# SH3_-_USB.net
KiCad netlist of a schematic drawn in Altium Designer
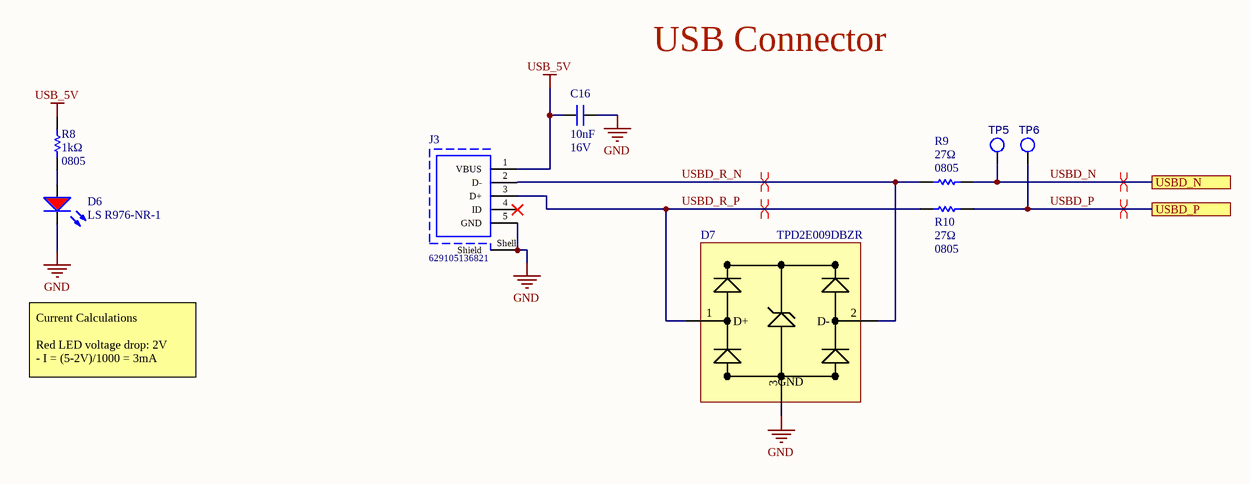
[diagram p0: SH3 - USB.SchDoc]

(export (version "E")
  (design (tool "Eeschema 10.0.6"))
  (components
    (comp (ref "C16")
      (value "CAP_10nF_16V_0805")
      (footprint "CAP2012")
      (description "CAP CER 10000PF 16V X7R 0805")
      (fields
        (field (name "VOLTAGE RATING") "16V")
        (field (name "TOLERANCE") "10%")
        (field (name "CAPACITANCE") "10nF")
      )
      (libsource (lib "UWRT_Schematic_Library_2020") (part "CAP_10nF_16V_0805"))
    )
    (comp (ref "D6")
      (value "LS R976-NR-1")
      (footprint "LED_0805_RED")
      (description "LED RED DIFFUSED 0805 SMD")
      (libsource (lib "UWRT_Schematic_Library_2020") (part "DIO_LED_R"))
    )
    (comp (ref "D7")
      (value "TVS_DIODE_USB_5.5V")
      (footprint "SOT23-3")
      (description "ESD Suppressor Diode Arrays 8KV 3-Pin SOT-23 T/R")
      (fields
        (field (name "MANUFACTURER") "Texas Instruments")
        (field (name "MANUFACTURER PART NUMBER") "TPD2E009DBZR")
      )
      (libsource (lib "UWRT_Schematic_Library_2020") (part "TVS_DIODE_USB_5.5V"))
    )
    (comp (ref "J3")
      (value "629105136821")
      (footprint "629105136821")
      (description "Micro USB 2.0 Type B Receptacle WR-COM, Horizontal, SMT, with Pads and Pegs")
      (fields (field (name "MANUFACTURER") "Wurth Elektronik") (field (name "PUBLISHER") "WurthElektronik"))
      (libsource (lib "Altium Content Vault") (part "WE-USB-5-1SHLD"))
    )
    (comp (ref "R8")
      (value "RES_1kΩ_0805_1%")
      (footprint "RESC0805")
      (description "RES 1K OHM 1% 1/8W 0805")
      (fields
        (field (name "RESISTANCE") "1kΩ")
        (field (name "TOLERANCE") "1%")
        (field (name "CASE CODE (IMPERIAL)") "0805")
      )
      (libsource (lib "UWRT_Schematic_Library_2020") (part "RES_1kΩ_0805_1%"))
    )
    (comp (ref "R9")
      (value "RES_27Ω_0805")
      (footprint "RESC0805")
      (description "RES 27 OHM 1% 1/8W 0805")
      (fields
        (field (name "TOLERANCE") "1%")
        (field (name "RESISTANCE") "27Ω")
        (field (name "CASE/PACKAGE") "0805")
      )
      (libsource (lib "UWRT_Schematic_Library_2020") (part "RES_27Ω_0805_1%"))
    )
    (comp (ref "R10")
      (value "RES_27Ω_0805")
      (footprint "RESC0805")
      (description "RES 27 OHM 1% 1/8W 0805")
      (fields
        (field (name "TOLERANCE") "1%")
        (field (name "RESISTANCE") "27Ω")
        (field (name "CASE/PACKAGE") "0805")
      )
      (libsource (lib "UWRT_Schematic_Library_2020") (part "RES_27Ω_0805_1%"))
    )
    (comp (ref "TP5")
      (value "TESTPOINT_LOOP")
      (footprint "TESTPOINT_LOOP")
      (description "Loop testpoint through-hole pad")
      (libsource (lib "UWRT_Schematic_Library_2020") (part "TESTPOINT_LOOP"))
    )
    (comp (ref "TP6")
      (value "TESTPOINT_LOOP")
      (footprint "TESTPOINT_LOOP")
      (description "Loop testpoint through-hole pad")
      (libsource (lib "UWRT_Schematic_Library_2020") (part "TESTPOINT_LOOP"))
    )
  )
  (nets
    (net (code "1") (name "/USBD_N") (class "Default")
      (node (ref "R9") (pin "2") (pinfunction "2_2") (pintype "passive"))
      (node (ref "TP5") (pin "1") (pintype "passive"))
    )
    (net (code "2") (name "/USBD_P") (class "Default")
      (node (ref "R10") (pin "2") (pinfunction "2_2") (pintype "passive"))
      (node (ref "TP6") (pin "1") (pintype "passive"))
    )
    (net (code "3") (name "/USBD_R_N") (class "Default")
      (node (ref "D7") (pin "2") (pinfunction "D-_2") (pintype "passive"))
      (node (ref "J3") (pin "2") (pinfunction "D-_2") (pintype "passive"))
      (node (ref "R9") (pin "1") (pinfunction "1_1") (pintype "passive"))
    )
    (net (code "4") (name "/USBD_R_P") (class "Default")
      (node (ref "D7") (pin "1") (pinfunction "D+_1") (pintype "passive"))
      (node (ref "J3") (pin "3") (pinfunction "D+_3") (pintype "passive"))
      (node (ref "R10") (pin "1") (pinfunction "1_1") (pintype "passive"))
    )
    (net (code "5") (name "GND") (class "Default")
      (node (ref "C16") (pin "2") (pinfunction "2_2") (pintype "passive"))
      (node (ref "D6") (pin "2") (pinfunction "K_2") (pintype "passive"))
      (node (ref "D7") (pin "3") (pinfunction "GND_3") (pintype "passive"))
      (node (ref "J3") (pin "5") (pinfunction "GND_5") (pintype "passive"))
      (node (ref "J3") (pin "Shell") (pinfunction "Shield_Shell") (pintype "passive"))
    )
    (net (code "6") (name "Net-(D6-A)") (class "Default")
      (node (ref "D6") (pin "1") (pinfunction "A_1") (pintype "passive"))
      (node (ref "R8") (pin "1") (pinfunction "1_1") (pintype "passive"))
    )
    (net (code "7") (name "USB_5V") (class "Default")
      (node (ref "C16") (pin "1") (pinfunction "1_1") (pintype "passive"))
      (node (ref "J3") (pin "1") (pinfunction "VBUS_1") (pintype "passive"))
      (node (ref "R8") (pin "2") (pinfunction "2_2") (pintype "passive"))
    )
    (net (code "8") (name "unconnected-(J3-ID-Pad4)") (class "Default")
      (node (ref "J3") (pin "4") (pinfunction "ID_4") (pintype "passive+no_connect"))
    )
  )
)
